# r_cepteur.net
KiCad netlist of a schematic drawn in EAGLE
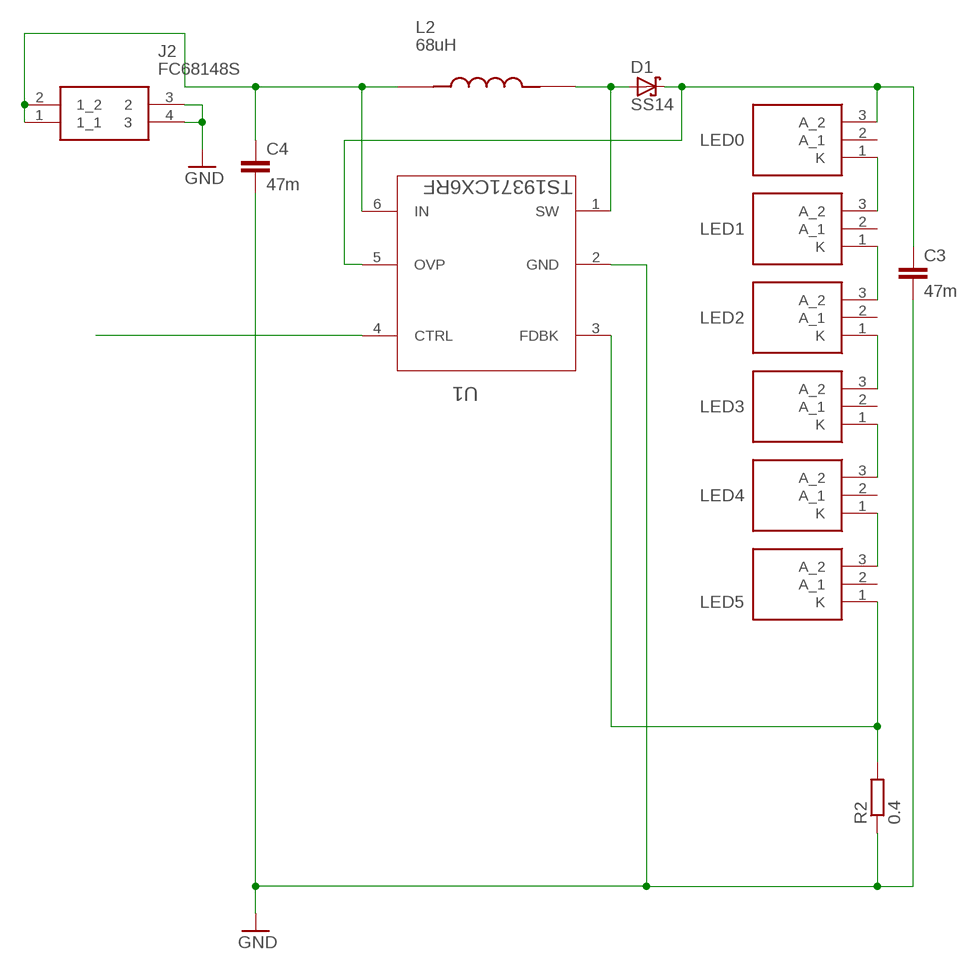
[diagram p0: schematic, sheet 1]

(export (version "E")
  (design (tool "Eeschema 10.0.6"))
  (components
    (comp (ref "C3")
      (value "47m")
      (footprint "eagle-import:C1206K")
      (libsource (lib "eagle-import") (part "C-EUC1206K"))
    )
    (comp (ref "C4")
      (value "47m")
      (footprint "eagle-import:C1206K")
      (libsource (lib "eagle-import") (part "C-EUC1206K"))
    )
    (comp (ref "D1")
      (value "SS14")
      (footprint "eagle-import:DO-214AC")
      (fields (field (name "MF") "ON Semiconductor"))
      (libsource (lib "eagle-import") (part "SS14"))
    )
    (comp (ref "J2")
      (value "FC68148S")
      (footprint "eagle-import:FC68148S_2")
      (libsource (lib "eagle-import") (part "FC68148S"))
    )
    (comp (ref "L2")
      (value "68uH")
      (footprint "eagle-import:IND_1255AY-680M=P3")
      (fields (field (name "MF") "Murata") (field (name "MP") "1255AY-680M=P3"))
      (libsource (lib "eagle-import") (part "1255AY-680M=P3"))
    )
    (comp (ref "LED0")
      (value "LED-CREE-JK3030")
      (footprint "eagle-import:JK3030AWT000000000A0HK230E")
      (fields
        (field (name "ARROW_PART_NUMBER") "JK3030AWT-00-0000-000A0HK230E")
        (field (name "MOUSER_PART_NUMBER") "941-JK3030W00A0HK230")
      )
      (libsource (lib "eagle-import") (part "LED-CREE-JK3030"))
    )
    (comp (ref "LED1")
      (value "LED-CREE-JK3030")
      (footprint "eagle-import:JK3030AWT000000000A0HK230E")
      (fields
        (field (name "ARROW_PART_NUMBER") "JK3030AWT-00-0000-000A0HK230E")
        (field (name "MOUSER_PART_NUMBER") "941-JK3030W00A0HK230")
      )
      (libsource (lib "eagle-import") (part "LED-CREE-JK3030"))
    )
    (comp (ref "LED2")
      (value "LED-CREE-JK3030")
      (footprint "eagle-import:JK3030AWT000000000A0HK230E")
      (fields
        (field (name "ARROW_PART_NUMBER") "JK3030AWT-00-0000-000A0HK230E")
        (field (name "MOUSER_PART_NUMBER") "941-JK3030W00A0HK230")
      )
      (libsource (lib "eagle-import") (part "LED-CREE-JK3030"))
    )
    (comp (ref "LED3")
      (value "LED-CREE-JK3030")
      (footprint "eagle-import:JK3030AWT000000000A0HK230E")
      (fields
        (field (name "ARROW_PART_NUMBER") "JK3030AWT-00-0000-000A0HK230E")
        (field (name "MOUSER_PART_NUMBER") "941-JK3030W00A0HK230")
      )
      (libsource (lib "eagle-import") (part "LED-CREE-JK3030"))
    )
    (comp (ref "LED4")
      (value "LED-CREE-JK3030")
      (footprint "eagle-import:JK3030AWT000000000A0HK230E")
      (fields
        (field (name "ARROW_PART_NUMBER") "JK3030AWT-00-0000-000A0HK230E")
        (field (name "MOUSER_PART_NUMBER") "941-JK3030W00A0HK230")
      )
      (libsource (lib "eagle-import") (part "LED-CREE-JK3030"))
    )
    (comp (ref "LED5")
      (value "LED-CREE-JK3030")
      (footprint "eagle-import:JK3030AWT000000000A0HK230E")
      (fields
        (field (name "ARROW_PART_NUMBER") "JK3030AWT-00-0000-000A0HK230E")
        (field (name "MOUSER_PART_NUMBER") "941-JK3030W00A0HK230")
      )
      (libsource (lib "eagle-import") (part "LED-CREE-JK3030"))
    )
    (comp (ref "R2")
      (value "0.4")
      (footprint "eagle-import:R1206")
      (libsource (lib "eagle-import") (part "R-EU_R1206"))
    )
    (comp (ref "U1")
      (value "TS19371CX6RF")
      (footprint "eagle-import:SOT95P280X125-6N")
      (libsource (lib "eagle-import") (part "TS19371CX6RF"))
    )
  )
  (nets
    (net (code "1") (name "GND") (class "Default")
      (node (ref "C3") (pin "2") (pinfunction "2_2") (pintype "passive"))
      (node (ref "C4") (pin "2") (pinfunction "2_2") (pintype "passive"))
      (node (ref "J2") (pin "3") (pinfunction "2_3") (pintype "bidirectional"))
      (node (ref "J2") (pin "4") (pinfunction "3_4") (pintype "bidirectional"))
      (node (ref "R2") (pin "1") (pinfunction "1_1") (pintype "passive"))
      (node (ref "U1") (pin "2") (pinfunction "GND_2") (pintype "input"))
    )
    (net (code "2") (name "Net-(J2-1_1)") (class "Default")
      (node (ref "C4") (pin "1") (pinfunction "1_1") (pintype "passive"))
      (node (ref "J2") (pin "1") (pinfunction "1_1_1") (pintype "bidirectional"))
      (node (ref "J2") (pin "2") (pinfunction "1_2_2") (pintype "bidirectional"))
      (node (ref "L2") (pin "1") (pinfunction "1_1") (pintype "passive"))
      (node (ref "U1") (pin "6") (pinfunction "IN_6") (pintype "input"))
    )
    (net (code "3") (name "Net-(LED0-A_2)") (class "Default")
      (node (ref "C3") (pin "1") (pinfunction "1_1") (pintype "passive"))
      (node (ref "D1") (pin "K") (pinfunction "K_K") (pintype "passive"))
      (node (ref "LED0") (pin "3") (pinfunction "A_2_3") (pintype "bidirectional"))
      (node (ref "U1") (pin "5") (pinfunction "OVP_5") (pintype "input"))
    )
    (net (code "4") (name "Net-(LED0-K)") (class "Default")
      (node (ref "LED0") (pin "1") (pinfunction "K_1") (pintype "bidirectional"))
      (node (ref "LED1") (pin "3") (pinfunction "A_2_3") (pintype "bidirectional"))
    )
    (net (code "5") (name "Net-(LED1-K)") (class "Default")
      (node (ref "LED1") (pin "1") (pinfunction "K_1") (pintype "bidirectional"))
      (node (ref "LED2") (pin "3") (pinfunction "A_2_3") (pintype "bidirectional"))
    )
    (net (code "6") (name "Net-(LED2-K)") (class "Default")
      (node (ref "LED2") (pin "1") (pinfunction "K_1") (pintype "bidirectional"))
      (node (ref "LED3") (pin "3") (pinfunction "A_2_3") (pintype "bidirectional"))
    )
    (net (code "7") (name "Net-(LED3-K)") (class "Default")
      (node (ref "LED3") (pin "1") (pinfunction "K_1") (pintype "bidirectional"))
      (node (ref "LED4") (pin "3") (pinfunction "A_2_3") (pintype "bidirectional"))
    )
    (net (code "8") (name "Net-(LED4-K)") (class "Default")
      (node (ref "LED4") (pin "1") (pinfunction "K_1") (pintype "bidirectional"))
      (node (ref "LED5") (pin "3") (pinfunction "A_2_3") (pintype "bidirectional"))
    )
    (net (code "9") (name "Net-(LED5-K)") (class "Default")
      (node (ref "LED5") (pin "1") (pinfunction "K_1") (pintype "bidirectional"))
      (node (ref "R2") (pin "2") (pinfunction "2_2") (pintype "passive"))
      (node (ref "U1") (pin "3") (pinfunction "FDBK_3") (pintype "input"))
    )
    (net (code "10") (name "Net-(U1-SW)") (class "Default")
      (node (ref "D1") (pin "A") (pinfunction "A_A") (pintype "passive"))
      (node (ref "L2") (pin "2") (pinfunction "2_2") (pintype "passive"))
      (node (ref "U1") (pin "1") (pinfunction "SW_1") (pintype "output"))
    )
    (net (code "11") (name "unconnected-(LED0-A_1-Pad2)") (class "Default")
      (node (ref "LED0") (pin "2") (pinfunction "A_1_2") (pintype "bidirectional"))
    )
    (net (code "12") (name "unconnected-(LED1-A_1-Pad2)") (class "Default")
      (node (ref "LED1") (pin "2") (pinfunction "A_1_2") (pintype "bidirectional"))
    )
    (net (code "13") (name "unconnected-(LED2-A_1-Pad2)") (class "Default")
      (node (ref "LED2") (pin "2") (pinfunction "A_1_2") (pintype "bidirectional"))
    )
    (net (code "14") (name "unconnected-(LED3-A_1-Pad2)") (class "Default")
      (node (ref "LED3") (pin "2") (pinfunction "A_1_2") (pintype "bidirectional"))
    )
    (net (code "15") (name "unconnected-(LED4-A_1-Pad2)") (class "Default")
      (node (ref "LED4") (pin "2") (pinfunction "A_1_2") (pintype "bidirectional"))
    )
    (net (code "16") (name "unconnected-(LED5-A_1-Pad2)") (class "Default")
      (node (ref "LED5") (pin "2") (pinfunction "A_1_2") (pintype "bidirectional"))
    )
    (net (code "17") (name "unconnected-(U1-CTRL-Pad4)") (class "Default")
      (node (ref "U1") (pin "4") (pinfunction "CTRL_4") (pintype "input"))
    )
  )
)
